# FridgeExtender.net
KiCad netlist of a schematic drawn in EAGLE
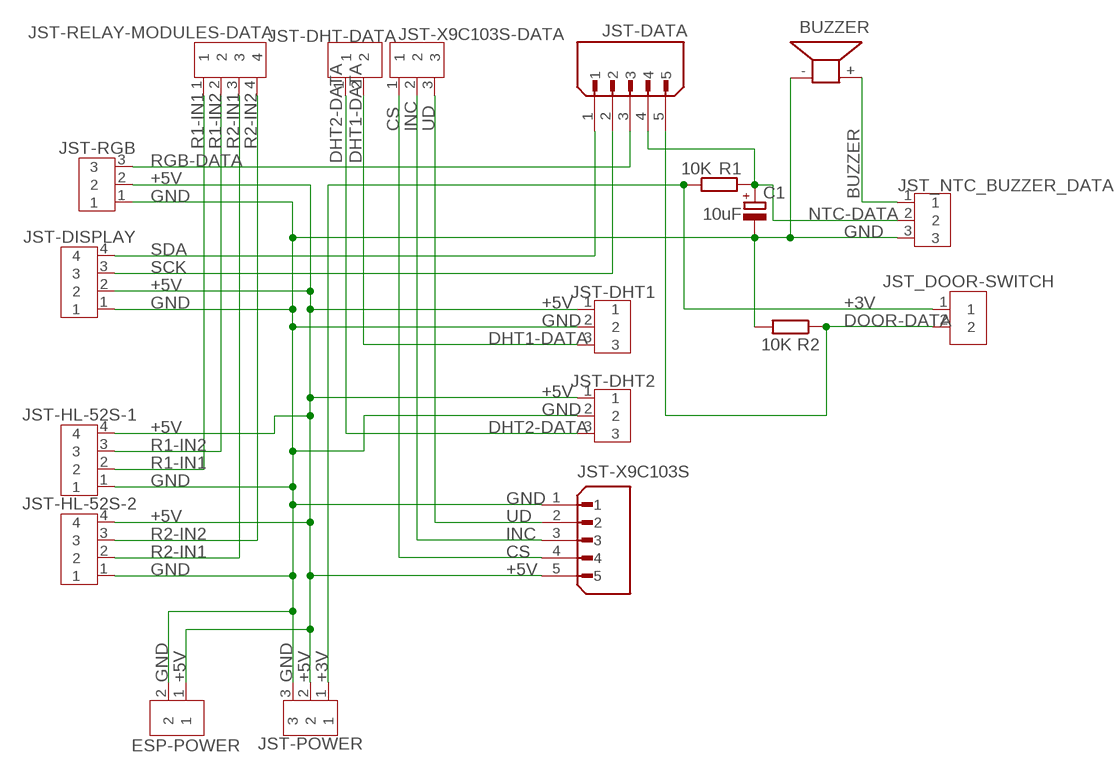
[diagram p0: schematic, sheet 1]

(export (version "E")
  (design (tool "Eeschema 10.0.6"))
  (components
    (comp (ref "BUZZER")
      (value "AL11P")
      (footprint "eagle-import:AL11P")
      (libsource (lib "eagle-import") (part "AL11P"))
    )
    (comp (ref "C1")
      (value "10uF")
      (footprint "eagle-import:CAPPRD508W65D1000H1100B")
      (libsource (lib "eagle-import") (part "C-POLRADIAL-11MM-DIA_"))
    )
    (comp (ref "ESP-POWER")
      (value "B2B-XH-A")
      (footprint "eagle-import:B2B-XH-A")
      (fields
        (field (name "MANUFACTURER") "JST Sales America Inc. ")
        (field (name "MPN") "B2B-XH-A(LF)(SN) ")
      )
      (libsource (lib "eagle-import") (part "B2B-XH-A"))
    )
    (comp (ref "JST-DATA")
      (value "B5B-XH-A(LF)(SN)")
      (footprint "eagle-import:JST_B5B-XH-A(LF)(SN)")
      (fields (field (name "MF") "JST Sales America Inc."))
      (libsource (lib "eagle-import") (part "B5B-XH-A(LF)(SN)"))
    )
    (comp (ref "JST-DHT-DATA")
      (value "B2B-XH-A")
      (footprint "eagle-import:B2B-XH-A")
      (fields
        (field (name "MANUFACTURER") "JST Sales America Inc. ")
        (field (name "MPN") "B2B-XH-A(LF)(SN) ")
      )
      (libsource (lib "eagle-import") (part "B2B-XH-A"))
    )
    (comp (ref "JST-DHT1")
      (value "B3B-XH-A")
      (footprint "eagle-import:B3B-XH-A")
      (fields (field (name "MANUFACTURER") "JST Sales America Inc. ") (field (name "MPN") "B3B-XH-A(LF)(SN)"))
      (libsource (lib "eagle-import") (part "B3B-XH-A"))
    )
    (comp (ref "JST-DHT2")
      (value "B3B-XH-A")
      (footprint "eagle-import:B3B-XH-A")
      (fields (field (name "MANUFACTURER") "JST Sales America Inc. ") (field (name "MPN") "B3B-XH-A(LF)(SN)"))
      (libsource (lib "eagle-import") (part "B3B-XH-A"))
    )
    (comp (ref "JST-DISPLAY")
      (value "B4B-XH-A")
      (footprint "eagle-import:B4B-XH-A")
      (fields (field (name "MANUFACTURER") "JST Sales America Inc.") (field (name "MPN") "B4B-XH-A(LF)(SN)"))
      (libsource (lib "eagle-import") (part "B4B-XH-A"))
    )
    (comp (ref "JST-HL-52S-1")
      (value "B4B-XH-A")
      (footprint "eagle-import:B4B-XH-A")
      (fields (field (name "MANUFACTURER") "JST Sales America Inc.") (field (name "MPN") "B4B-XH-A(LF)(SN)"))
      (libsource (lib "eagle-import") (part "B4B-XH-A"))
    )
    (comp (ref "JST-HL-52S-2")
      (value "B4B-XH-A")
      (footprint "eagle-import:B4B-XH-A")
      (fields (field (name "MANUFACTURER") "JST Sales America Inc.") (field (name "MPN") "B4B-XH-A(LF)(SN)"))
      (libsource (lib "eagle-import") (part "B4B-XH-A"))
    )
    (comp (ref "JST-POWER")
      (value "B3B-XH-A")
      (footprint "eagle-import:B3B-XH-A")
      (fields (field (name "MANUFACTURER") "JST Sales America Inc. ") (field (name "MPN") "B3B-XH-A(LF)(SN)"))
      (libsource (lib "eagle-import") (part "B3B-XH-A"))
    )
    (comp (ref "JST-RELAY-MODULES-DATA")
      (value "B4B-XH-A")
      (footprint "eagle-import:B4B-XH-A")
      (fields (field (name "MANUFACTURER") "JST Sales America Inc.") (field (name "MPN") "B4B-XH-A(LF)(SN)"))
      (libsource (lib "eagle-import") (part "B4B-XH-A"))
    )
    (comp (ref "JST-RGB")
      (value "B3B-XH-A")
      (footprint "eagle-import:B3B-XH-A")
      (fields (field (name "MANUFACTURER") "JST Sales America Inc. ") (field (name "MPN") "B3B-XH-A(LF)(SN)"))
      (libsource (lib "eagle-import") (part "B3B-XH-A"))
    )
    (comp (ref "JST-X9C103S")
      (value "B5B-XH-A(LF)(SN)")
      (footprint "eagle-import:JST_B5B-XH-A(LF)(SN)")
      (fields (field (name "MF") "JST Sales America Inc."))
      (libsource (lib "eagle-import") (part "B5B-XH-A(LF)(SN)"))
    )
    (comp (ref "JST-X9C103S-DATA")
      (value "B3B-XH-A")
      (footprint "eagle-import:B3B-XH-A")
      (fields (field (name "MANUFACTURER") "JST Sales America Inc. ") (field (name "MPN") "B3B-XH-A(LF)(SN)"))
      (libsource (lib "eagle-import") (part "B3B-XH-A"))
    )
    (comp (ref "JST_DOOR-SWITCH")
      (value "B2B-XH-A")
      (footprint "eagle-import:B2B-XH-A")
      (fields
        (field (name "MANUFACTURER") "JST Sales America Inc. ")
        (field (name "MPN") "B2B-XH-A(LF)(SN) ")
      )
      (libsource (lib "eagle-import") (part "B2B-XH-A"))
    )
    (comp (ref "JST_NTC_BUZZER_DATA")
      (value "B3B-XH-A")
      (footprint "eagle-import:B3B-XH-A")
      (fields (field (name "MANUFACTURER") "JST Sales America Inc. ") (field (name "MPN") "B3B-XH-A(LF)(SN)"))
      (libsource (lib "eagle-import") (part "B3B-XH-A"))
    )
    (comp (ref "R1")
      (value "10K")
      (footprint "eagle-import:RESAD724W46L381D178B")
      (libsource (lib "eagle-import") (part "RAXIAL-7.2MM-PITCH_"))
    )
    (comp (ref "R2")
      (value "10K")
      (footprint "eagle-import:RESAD724W46L381D178B")
      (libsource (lib "eagle-import") (part "RAXIAL-7.2MM-PITCH_"))
    )
  )
  (nets
    (net (code "1") (name "/+3V") (class "Default")
      (node (ref "JST-POWER") (pin "1") (pinfunction "1_1") (pintype "bidirectional"))
      (node (ref "JST_DOOR-SWITCH") (pin "1") (pinfunction "1_1") (pintype "bidirectional"))
      (node (ref "R1") (pin "1") (pinfunction "1_1") (pintype "passive"))
    )
    (net (code "2") (name "/+5V") (class "Default")
      (node (ref "ESP-POWER") (pin "1") (pinfunction "1_1") (pintype "bidirectional"))
      (node (ref "JST-DHT1") (pin "1") (pinfunction "1_1") (pintype "bidirectional"))
      (node (ref "JST-DHT2") (pin "1") (pinfunction "1_1") (pintype "bidirectional"))
      (node (ref "JST-DISPLAY") (pin "2") (pinfunction "2_2") (pintype "bidirectional"))
      (node (ref "JST-HL-52S-1") (pin "4") (pinfunction "4_4") (pintype "bidirectional"))
      (node (ref "JST-HL-52S-2") (pin "4") (pinfunction "4_4") (pintype "bidirectional"))
      (node (ref "JST-POWER") (pin "2") (pinfunction "2_2") (pintype "bidirectional"))
      (node (ref "JST-RGB") (pin "2") (pinfunction "2_2") (pintype "bidirectional"))
      (node (ref "JST-X9C103S") (pin "5") (pinfunction "5_5") (pintype "passive"))
    )
    (net (code "3") (name "/BUZZER") (class "Default")
      (node (ref "BUZZER") (pin "+") (pinfunction "2_+") (pintype "passive"))
      (node (ref "JST_NTC_BUZZER_DATA") (pin "1") (pinfunction "1_1") (pintype "bidirectional"))
    )
    (net (code "4") (name "/CS") (class "Default")
      (node (ref "JST-X9C103S") (pin "4") (pinfunction "4_4") (pintype "passive"))
      (node (ref "JST-X9C103S-DATA") (pin "1") (pinfunction "1_1") (pintype "bidirectional"))
    )
    (net (code "5") (name "/DHT1-DATA") (class "Default")
      (node (ref "JST-DHT-DATA") (pin "2") (pinfunction "2_2") (pintype "bidirectional"))
      (node (ref "JST-DHT1") (pin "3") (pinfunction "3_3") (pintype "bidirectional"))
    )
    (net (code "6") (name "/DHT2-DATA") (class "Default")
      (node (ref "JST-DHT-DATA") (pin "1") (pinfunction "1_1") (pintype "bidirectional"))
      (node (ref "JST-DHT2") (pin "3") (pinfunction "3_3") (pintype "bidirectional"))
    )
    (net (code "7") (name "/DOOR-DATA") (class "Default")
      (node (ref "JST-DATA") (pin "5") (pinfunction "5_5") (pintype "passive"))
      (node (ref "JST_DOOR-SWITCH") (pin "2") (pinfunction "2_2") (pintype "bidirectional"))
      (node (ref "R2") (pin "1") (pinfunction "1_1") (pintype "passive"))
    )
    (net (code "8") (name "/GND") (class "Default")
      (node (ref "BUZZER") (pin "-") (pinfunction "1_-") (pintype "passive"))
      (node (ref "C1") (pin "2") (pinfunction "-_2") (pintype "passive"))
      (node (ref "ESP-POWER") (pin "2") (pinfunction "2_2") (pintype "bidirectional"))
      (node (ref "JST-DHT1") (pin "2") (pinfunction "2_2") (pintype "bidirectional"))
      (node (ref "JST-DHT2") (pin "2") (pinfunction "2_2") (pintype "bidirectional"))
      (node (ref "JST-DISPLAY") (pin "1") (pinfunction "1_1") (pintype "bidirectional"))
      (node (ref "JST-HL-52S-1") (pin "1") (pinfunction "1_1") (pintype "bidirectional"))
      (node (ref "JST-HL-52S-2") (pin "1") (pinfunction "1_1") (pintype "bidirectional"))
      (node (ref "JST-POWER") (pin "3") (pinfunction "3_3") (pintype "bidirectional"))
      (node (ref "JST-RGB") (pin "1") (pinfunction "1_1") (pintype "bidirectional"))
      (node (ref "JST-X9C103S") (pin "1") (pinfunction "1_1") (pintype "passive"))
      (node (ref "JST_NTC_BUZZER_DATA") (pin "3") (pinfunction "3_3") (pintype "bidirectional"))
      (node (ref "R2") (pin "2") (pinfunction "2_2") (pintype "passive"))
    )
    (net (code "9") (name "/INC") (class "Default")
      (node (ref "JST-X9C103S") (pin "3") (pinfunction "3_3") (pintype "passive"))
      (node (ref "JST-X9C103S-DATA") (pin "2") (pinfunction "2_2") (pintype "bidirectional"))
    )
    (net (code "10") (name "/NTC-DATA") (class "Default")
      (node (ref "C1") (pin "1") (pinfunction "+_1") (pintype "passive"))
      (node (ref "JST-DATA") (pin "4") (pinfunction "4_4") (pintype "passive"))
      (node (ref "JST_NTC_BUZZER_DATA") (pin "2") (pinfunction "2_2") (pintype "bidirectional"))
      (node (ref "R1") (pin "2") (pinfunction "2_2") (pintype "passive"))
    )
    (net (code "11") (name "/R1-IN1") (class "Default")
      (node (ref "JST-HL-52S-1") (pin "2") (pinfunction "2_2") (pintype "bidirectional"))
      (node (ref "JST-RELAY-MODULES-DATA") (pin "1") (pinfunction "1_1") (pintype "bidirectional"))
    )
    (net (code "12") (name "/R1-IN2") (class "Default")
      (node (ref "JST-HL-52S-1") (pin "3") (pinfunction "3_3") (pintype "bidirectional"))
      (node (ref "JST-RELAY-MODULES-DATA") (pin "2") (pinfunction "2_2") (pintype "bidirectional"))
    )
    (net (code "13") (name "/R2-IN1") (class "Default")
      (node (ref "JST-HL-52S-2") (pin "2") (pinfunction "2_2") (pintype "bidirectional"))
      (node (ref "JST-RELAY-MODULES-DATA") (pin "3") (pinfunction "3_3") (pintype "bidirectional"))
    )
    (net (code "14") (name "/R2-IN2") (class "Default")
      (node (ref "JST-HL-52S-2") (pin "3") (pinfunction "3_3") (pintype "bidirectional"))
      (node (ref "JST-RELAY-MODULES-DATA") (pin "4") (pinfunction "4_4") (pintype "bidirectional"))
    )
    (net (code "15") (name "/RGB-DATA") (class "Default")
      (node (ref "JST-DATA") (pin "3") (pinfunction "3_3") (pintype "passive"))
      (node (ref "JST-RGB") (pin "3") (pinfunction "3_3") (pintype "bidirectional"))
    )
    (net (code "16") (name "/SCK") (class "Default")
      (node (ref "JST-DATA") (pin "2") (pinfunction "2_2") (pintype "passive"))
      (node (ref "JST-DISPLAY") (pin "3") (pinfunction "3_3") (pintype "bidirectional"))
    )
    (net (code "17") (name "/SDA") (class "Default")
      (node (ref "JST-DATA") (pin "1") (pinfunction "1_1") (pintype "passive"))
      (node (ref "JST-DISPLAY") (pin "4") (pinfunction "4_4") (pintype "bidirectional"))
    )
    (net (code "18") (name "/UD") (class "Default")
      (node (ref "JST-X9C103S") (pin "2") (pinfunction "2_2") (pintype "passive"))
      (node (ref "JST-X9C103S-DATA") (pin "3") (pinfunction "3_3") (pintype "bidirectional"))
    )
  )
)
